# Dashlight.net
KiCad netlist of a schematic drawn in EasyEDA
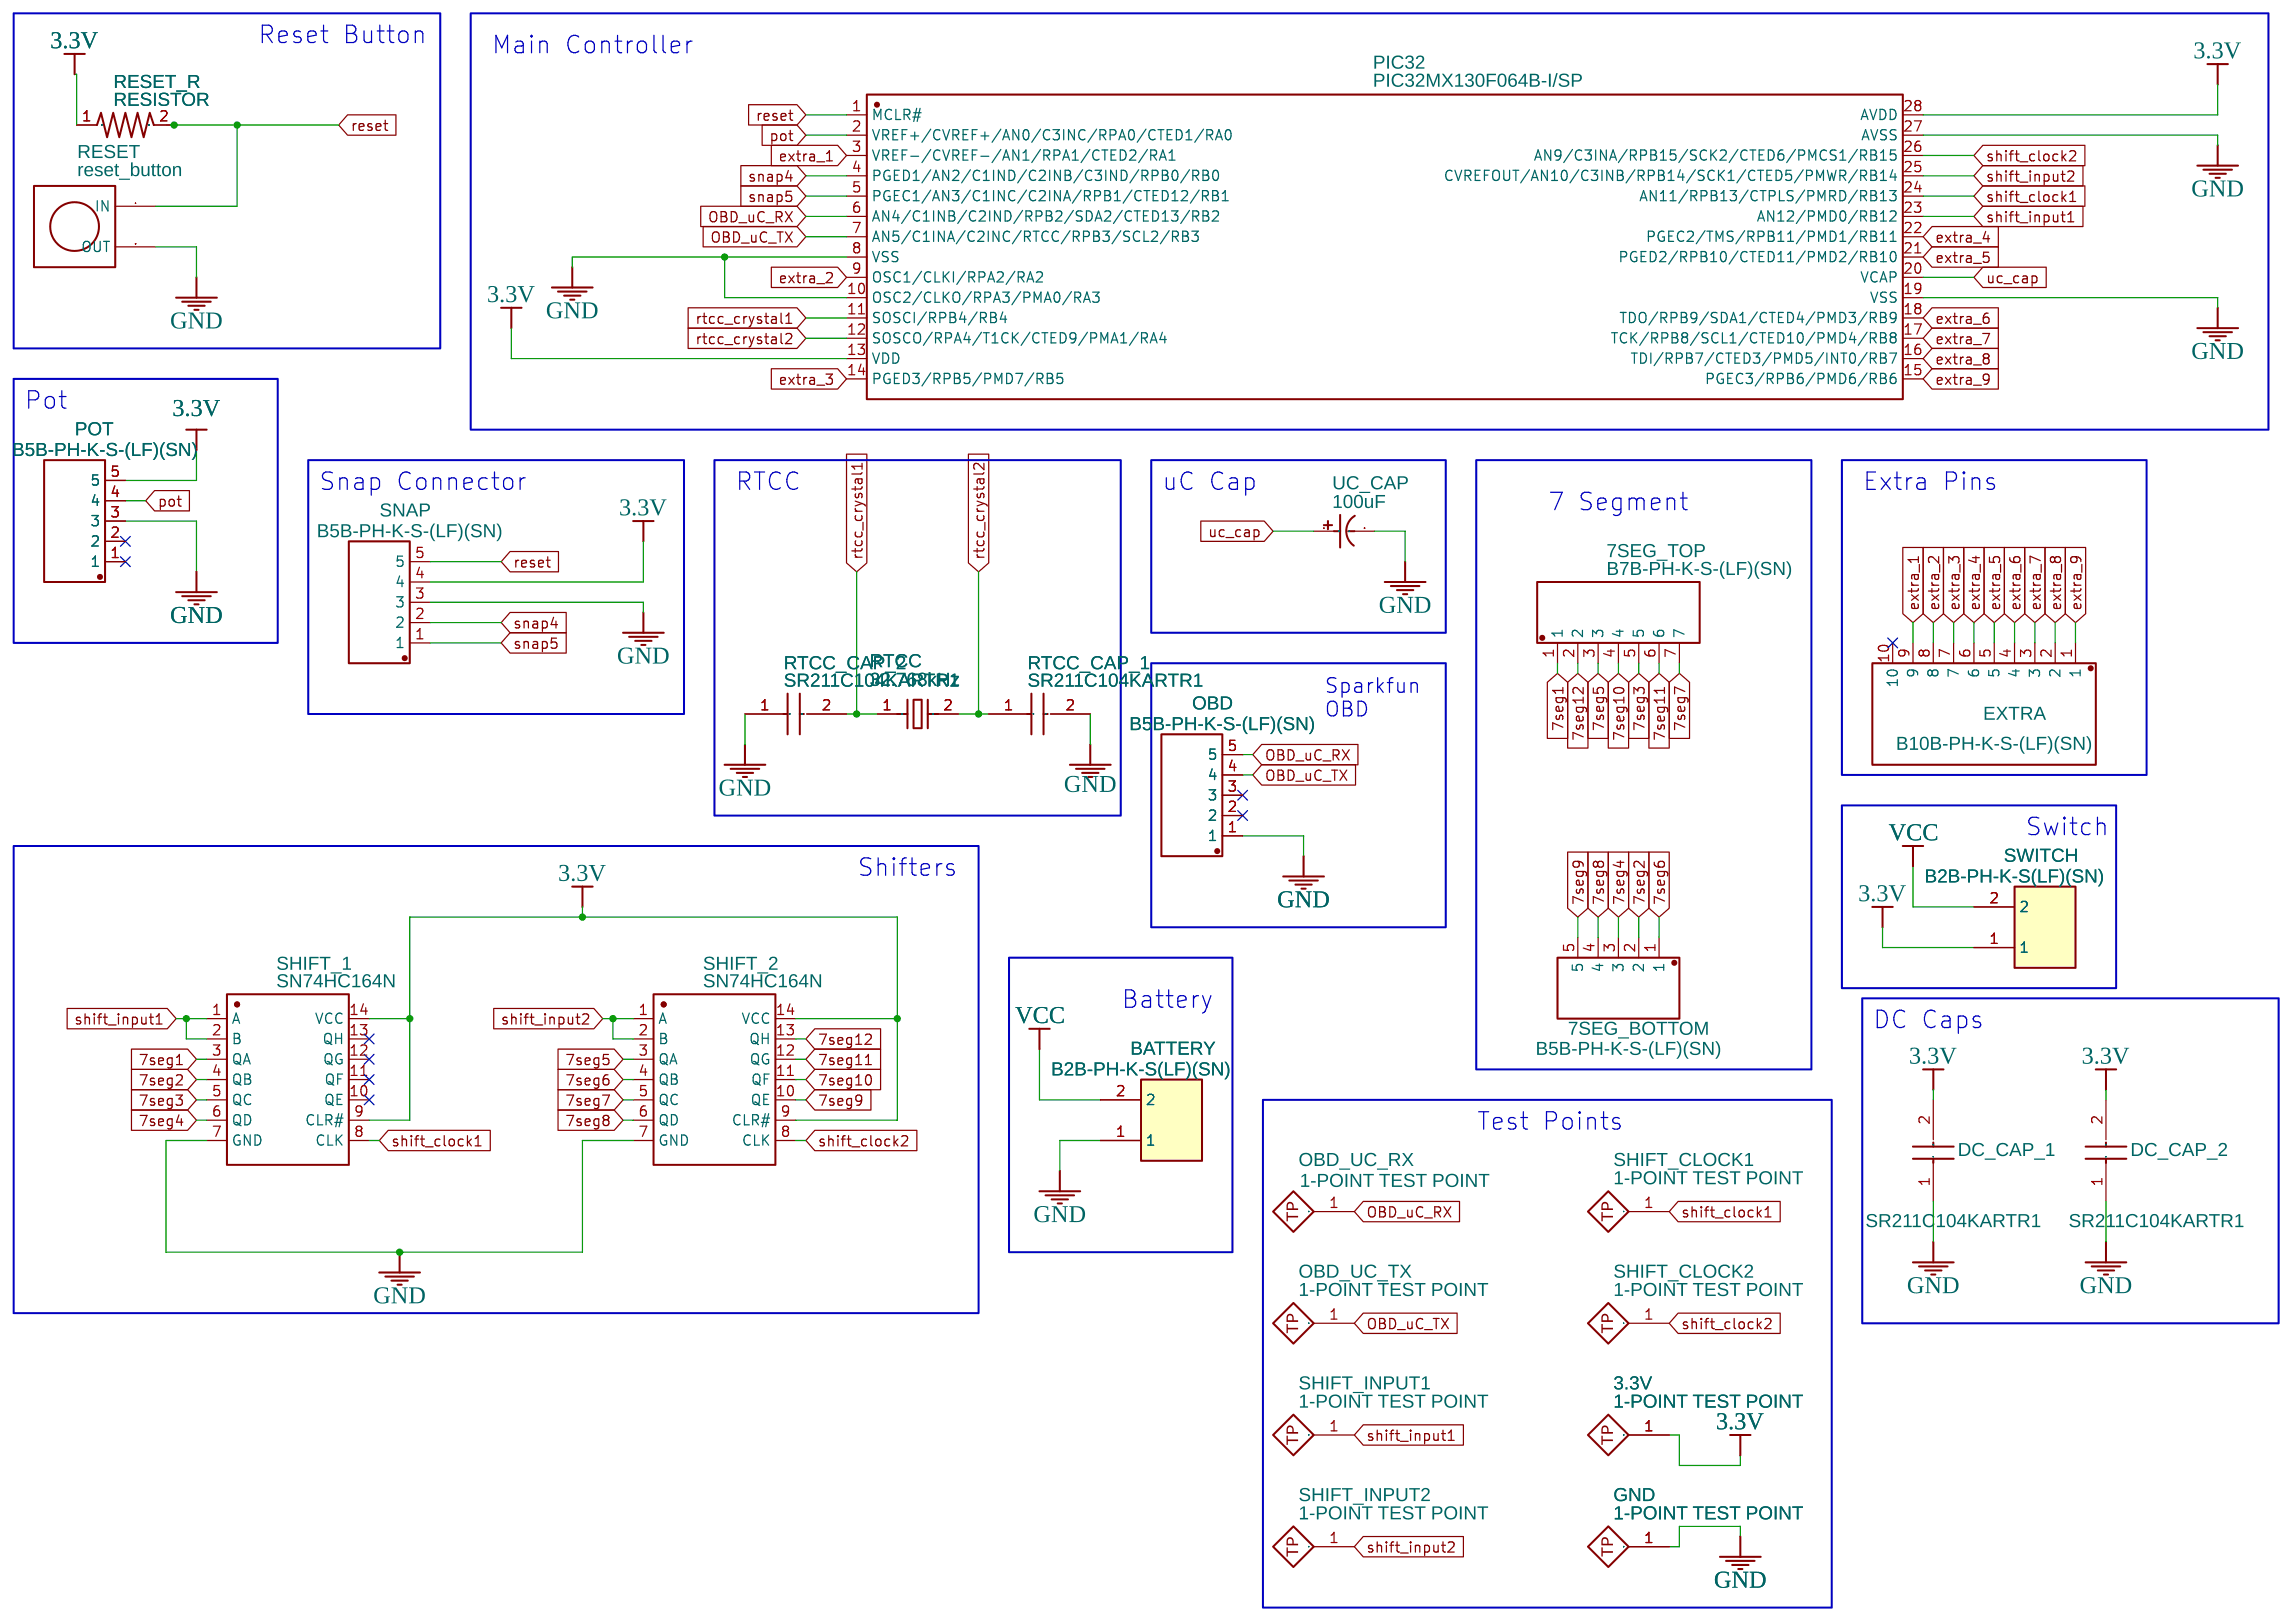
[diagram p0: schematic sheet]

(export (version "E")
  (design (tool "Eeschema 10.0.6"))
  (components
    (comp (ref "3.3V") (value "1-POINT TEST POINT") (libsource (lib "") (part "1-POINT TEST POINT_4")))
    (comp (ref "7SEG_BOTTOM")
      (value "B5B-PH-K-S-(LF)(SN)")
      (fields (field (name "Manufacturer Part") "B5B-PH-K-S(LF)(SN)") (field (name "Manufacturer") "JST"))
      (libsource (lib "") (part "B5B-PH-K-S-(LF)(SN)_1"))
    )
    (comp (ref "7SEG_TOP")
      (value "B7B-PH-K-S-(LF)(SN)")
      (fields (field (name "Manufacturer Part") "B7B-PH-K-S(LF)(SN)") (field (name "Manufacturer") "JST"))
      (libsource (lib "") (part "B7B-PH-K-S-(LF)(SN)"))
    )
    (comp (ref "BATTERY")
      (value "B2B-PH-K-S(LF)(SN)")
      (fields (field (name "Manufacturer") "JST"))
      (libsource (lib "") (part "B2B-PH-K-S(LF)(SN)_1"))
    )
    (comp (ref "DC_CAP_1") (value "SR211C104KARTR1") (libsource (lib "") (part "SR211C104KARTR1")))
    (comp (ref "DC_CAP_2") (value "SR211C104KARTR1") (libsource (lib "") (part "SR211C104KARTR1")))
    (comp (ref "EXTRA")
      (value "B10B-PH-K-S-(LF)(SN)")
      (fields (field (name "Manufacturer Part") "B10B-PH-K-S(LF)(SN)") (field (name "Manufacturer") "JST"))
      (libsource (lib "") (part "B10B-PH-K-S-(LF)(SN)"))
    )
    (comp (ref "GND") (value "1-POINT TEST POINT") (libsource (lib "") (part "1-POINT TEST POINT_6")))
    (comp (ref "OBD")
      (value "B5B-PH-K-S-(LF)(SN)")
      (fields (field (name "Manufacturer Part") "B5B-PH-K-S(LF)(SN)") (field (name "Manufacturer") "JST"))
      (libsource (lib "") (part "B5B-PH-K-S-(LF)(SN)"))
    )
    (comp (ref "OBD_UC_RX") (value "1-POINT TEST POINT") (libsource (lib "") (part "1-POINT TEST POINT_5")))
    (comp (ref "OBD_UC_TX") (value "1-POINT TEST POINT") (libsource (lib "") (part "1-POINT TEST POINT_1")))
    (comp (ref "PIC32")
      (value "PIC32MX130F064B-I/SP")
      (fields (field (name "Manufacturer") "Microchip Tech"))
      (libsource (lib "") (part "PIC32MX130F064B-I/SP"))
    )
    (comp (ref "POT")
      (value "B5B-PH-K-S-(LF)(SN)")
      (fields (field (name "Manufacturer Part") "B5B-PH-K-S(LF)(SN)") (field (name "Manufacturer") "JST"))
      (libsource (lib "") (part "B5B-PH-K-S-(LF)(SN)_3"))
    )
    (comp (ref "RESET") (value "reset_button") (libsource (lib "") (part "Through-Hole 6x6mm Push Button")))
    (comp (ref "RESET_R") (value "RESISTOR") (libsource (lib "") (part "res")))
    (comp (ref "RTCC")
      (value "32.768kHz")
      (fields (field (name "Manufacturer Part") "MP2032K76812002") (field (name "Manufacturer") "HUAXIN(华昕)"))
      (libsource (lib "") (part "MP4032K76812002"))
    )
    (comp (ref "RTCC_CAP_1") (value "SR211C104KARTR1") (libsource (lib "") (part "SR211C104KARTR1_1")))
    (comp (ref "RTCC_CAP_2") (value "SR211C104KARTR1") (libsource (lib "") (part "SR211C104KARTR1_1")))
    (comp (ref "SHIFT_1")
      (value "SN74HC164N")
      (fields (field (name "Manufacturer") "TI(德州仪器)"))
      (libsource (lib "") (part "SN74HC164N"))
    )
    (comp (ref "SHIFT_2")
      (value "SN74HC164N")
      (fields (field (name "Manufacturer") "TI(德州仪器)"))
      (libsource (lib "") (part "SN74HC164N"))
    )
    (comp (ref "SHIFT_CLOCK1")
      (value "1-POINT TEST POINT")
      (libsource (lib "") (part "1-POINT TEST POINT_3"))
    )
    (comp (ref "SHIFT_CLOCK2")
      (value "1-POINT TEST POINT")
      (libsource (lib "") (part "1-POINT TEST POINT_2"))
    )
    (comp (ref "SHIFT_INPUT1") (value "1-POINT TEST POINT") (libsource (lib "") (part "1-POINT TEST POINT")))
    (comp (ref "SHIFT_INPUT2") (value "1-POINT TEST POINT") (libsource (lib "") (part "1-POINT TEST POINT")))
    (comp (ref "SNAP")
      (value "B5B-PH-K-S-(LF)(SN)")
      (fields (field (name "Manufacturer Part") "B5B-PH-K-S(LF)(SN)") (field (name "Manufacturer") "JST"))
      (libsource (lib "") (part "B5B-PH-K-S-(LF)(SN)_2"))
    )
    (comp (ref "SWITCH")
      (value "B2B-PH-K-S(LF)(SN)")
      (fields (field (name "Manufacturer") "JST"))
      (libsource (lib "") (part "B2B-PH-K-S(LF)(SN)"))
    )
    (comp (ref "UC_CAP")
      (value "100uF")
      (fields (field (name "Manufacturer Part") "100uF 10V 4*7") (field (name "Manufacturer") "LCSC"))
      (libsource (lib "") (part "100uF"))
    )
  )
  (nets
    (net (code "1") (name "3.3V") (class "Default")
      (node (ref "3.3V") (pin "1") (pinfunction "1_1") (pintype "unspecified"))
      (node (ref "DC_CAP_1") (pin "2") (pinfunction "2_2") (pintype "bidirectional"))
      (node (ref "DC_CAP_2") (pin "2") (pinfunction "2_2") (pintype "bidirectional"))
      (node (ref "PIC32") (pin "13") (pinfunction "VDD_13") (pintype "unspecified"))
      (node (ref "PIC32") (pin "28") (pinfunction "AVDD_28") (pintype "unspecified"))
      (node (ref "POT") (pin "5") (pinfunction "5_5") (pintype "unspecified"))
      (node (ref "RESET_R") (pin "1") (pinfunction "1_1") (pintype "unspecified"))
      (node (ref "SHIFT_1") (pin "14") (pinfunction "VCC_14") (pintype "unspecified"))
      (node (ref "SHIFT_1") (pin "9") (pinfunction "CLR#_9") (pintype "unspecified"))
      (node (ref "SHIFT_2") (pin "14") (pinfunction "VCC_14") (pintype "unspecified"))
      (node (ref "SHIFT_2") (pin "9") (pinfunction "CLR#_9") (pintype "unspecified"))
      (node (ref "SNAP") (pin "4") (pinfunction "4_4") (pintype "unspecified"))
      (node (ref "SWITCH") (pin "1") (pinfunction "1_1") (pintype "input"))
    )
    (net (code "2") (name "7seg1") (class "Default")
      (node (ref "7SEG_TOP") (pin "1") (pinfunction "1_1") (pintype "unspecified"))
      (node (ref "SHIFT_1") (pin "3") (pinfunction "QA_3") (pintype "unspecified"))
    )
    (net (code "3") (name "7seg2") (class "Default")
      (node (ref "7SEG_BOTTOM") (pin "2") (pinfunction "2_2") (pintype "unspecified"))
      (node (ref "SHIFT_1") (pin "4") (pinfunction "QB_4") (pintype "unspecified"))
    )
    (net (code "4") (name "7seg3") (class "Default")
      (node (ref "7SEG_TOP") (pin "5") (pinfunction "5_5") (pintype "unspecified"))
      (node (ref "SHIFT_1") (pin "5") (pinfunction "QC_5") (pintype "unspecified"))
    )
    (net (code "5") (name "7seg4") (class "Default")
      (node (ref "7SEG_BOTTOM") (pin "3") (pinfunction "3_3") (pintype "unspecified"))
      (node (ref "SHIFT_1") (pin "6") (pinfunction "QD_6") (pintype "unspecified"))
    )
    (net (code "6") (name "7seg5") (class "Default")
      (node (ref "7SEG_TOP") (pin "3") (pinfunction "3_3") (pintype "unspecified"))
      (node (ref "SHIFT_2") (pin "3") (pinfunction "QA_3") (pintype "unspecified"))
    )
    (net (code "7") (name "7seg6") (class "Default")
      (node (ref "7SEG_BOTTOM") (pin "1") (pinfunction "1_1") (pintype "unspecified"))
      (node (ref "SHIFT_2") (pin "4") (pinfunction "QB_4") (pintype "unspecified"))
    )
    (net (code "8") (name "7seg7") (class "Default")
      (node (ref "7SEG_TOP") (pin "7") (pinfunction "7_7") (pintype "unspecified"))
      (node (ref "SHIFT_2") (pin "5") (pinfunction "QC_5") (pintype "unspecified"))
    )
    (net (code "9") (name "7seg8") (class "Default")
      (node (ref "7SEG_BOTTOM") (pin "4") (pinfunction "4_4") (pintype "unspecified"))
      (node (ref "SHIFT_2") (pin "6") (pinfunction "QD_6") (pintype "unspecified"))
    )
    (net (code "10") (name "7seg9") (class "Default")
      (node (ref "7SEG_BOTTOM") (pin "5") (pinfunction "5_5") (pintype "unspecified"))
      (node (ref "SHIFT_2") (pin "10") (pinfunction "QE_10") (pintype "unspecified"))
    )
    (net (code "11") (name "7seg10") (class "Default")
      (node (ref "7SEG_TOP") (pin "4") (pinfunction "4_4") (pintype "unspecified"))
      (node (ref "SHIFT_2") (pin "11") (pinfunction "QF_11") (pintype "unspecified"))
    )
    (net (code "12") (name "7seg11") (class "Default")
      (node (ref "7SEG_TOP") (pin "6") (pinfunction "6_6") (pintype "unspecified"))
      (node (ref "SHIFT_2") (pin "12") (pinfunction "QG_12") (pintype "unspecified"))
    )
    (net (code "13") (name "7seg12") (class "Default")
      (node (ref "7SEG_TOP") (pin "2") (pinfunction "2_2") (pintype "unspecified"))
      (node (ref "SHIFT_2") (pin "13") (pinfunction "QH_13") (pintype "unspecified"))
    )
    (net (code "14") (name "GND") (class "Default")
      (node (ref "BATTERY") (pin "1") (pinfunction "1_1") (pintype "input"))
      (node (ref "DC_CAP_1") (pin "1") (pinfunction "1_1") (pintype "bidirectional"))
      (node (ref "DC_CAP_2") (pin "1") (pinfunction "1_1") (pintype "bidirectional"))
      (node (ref "GND") (pin "1") (pinfunction "1_1") (pintype "unspecified"))
      (node (ref "OBD") (pin "1") (pinfunction "1_1") (pintype "unspecified"))
      (node (ref "PIC32") (pin "10") (pinfunction "OSC2/CLKO/RPA3/PMA0/RA3_10") (pintype "unspecified"))
      (node (ref "PIC32") (pin "19") (pinfunction "VSS_19") (pintype "unspecified"))
      (node (ref "PIC32") (pin "27") (pinfunction "AVSS_27") (pintype "unspecified"))
      (node (ref "PIC32") (pin "8") (pinfunction "VSS_8") (pintype "unspecified"))
      (node (ref "POT") (pin "3") (pinfunction "3_3") (pintype "unspecified"))
      (node (ref "RESET") (pin "2") (pinfunction "OUT_2") (pintype "unspecified"))
      (node (ref "RTCC_CAP_1") (pin "2") (pinfunction "2_2") (pintype "bidirectional"))
      (node (ref "RTCC_CAP_2") (pin "1") (pinfunction "1_1") (pintype "bidirectional"))
      (node (ref "SHIFT_1") (pin "7") (pinfunction "GND_7") (pintype "unspecified"))
      (node (ref "SHIFT_2") (pin "7") (pinfunction "GND_7") (pintype "unspecified"))
      (node (ref "SNAP") (pin "3") (pinfunction "3_3") (pintype "unspecified"))
      (node (ref "UC_CAP") (pin "2") (pinfunction "2_2") (pintype "input"))
    )
    (net (code "15") (name "OBD_uC_RX") (class "Default")
      (node (ref "OBD") (pin "5") (pinfunction "5_5") (pintype "unspecified"))
      (node (ref "OBD_UC_RX") (pin "1") (pinfunction "1_1") (pintype "unspecified"))
      (node (ref "PIC32") (pin "6") (pinfunction "AN4/C1INB/C2IND/RPB2/SDA2/CTED13/RB2_6") (pintype "unspecified"))
    )
    (net (code "16") (name "OBD_uC_TX") (class "Default")
      (node (ref "OBD") (pin "4") (pinfunction "4_4") (pintype "unspecified"))
      (node (ref "OBD_UC_TX") (pin "1") (pinfunction "1_1") (pintype "unspecified"))
      (node (ref "PIC32") (pin "7") (pinfunction "AN5/C1INA/C2INC/RTCC/RPB3/SCL2/RB3_7") (pintype "unspecified"))
    )
    (net (code "17") (name "VCC") (class "Default")
      (node (ref "BATTERY") (pin "2") (pinfunction "2_2") (pintype "input"))
      (node (ref "SWITCH") (pin "2") (pinfunction "2_2") (pintype "input"))
    )
    (net (code "18") (name "extra_1") (class "Default")
      (node (ref "EXTRA") (pin "9") (pinfunction "9_9") (pintype "unspecified"))
      (node (ref "PIC32") (pin "3") (pinfunction "VREF-/CVREF-/AN1/RPA1/CTED2/RA1_3") (pintype "unspecified"))
    )
    (net (code "19") (name "extra_2") (class "Default")
      (node (ref "EXTRA") (pin "8") (pinfunction "8_8") (pintype "unspecified"))
      (node (ref "PIC32") (pin "9") (pinfunction "OSC1/CLKI/RPA2/RA2_9") (pintype "unspecified"))
    )
    (net (code "20") (name "extra_3") (class "Default")
      (node (ref "EXTRA") (pin "7") (pinfunction "7_7") (pintype "unspecified"))
      (node (ref "PIC32") (pin "14") (pinfunction "PGED3/RPB5/PMD7/RB5_14") (pintype "unspecified"))
    )
    (net (code "21") (name "extra_4") (class "Default")
      (node (ref "EXTRA") (pin "6") (pinfunction "6_6") (pintype "unspecified"))
      (node (ref "PIC32") (pin "22") (pinfunction "PGEC2/TMS/RPB11/PMD1/RB11_22") (pintype "unspecified"))
    )
    (net (code "22") (name "extra_5") (class "Default")
      (node (ref "EXTRA") (pin "5") (pinfunction "5_5") (pintype "unspecified"))
      (node (ref "PIC32") (pin "21") (pinfunction "PGED2/RPB10/CTED11/PMD2/RB10_21") (pintype "unspecified"))
    )
    (net (code "23") (name "extra_6") (class "Default")
      (node (ref "EXTRA") (pin "4") (pinfunction "4_4") (pintype "unspecified"))
      (node (ref "PIC32") (pin "18") (pinfunction "TDO/RPB9/SDA1/CTED4/PMD3/RB9_18") (pintype "unspecified"))
    )
    (net (code "24") (name "extra_7") (class "Default")
      (node (ref "EXTRA") (pin "3") (pinfunction "3_3") (pintype "unspecified"))
      (node (ref "PIC32") (pin "17") (pinfunction "TCK/RPB8/SCL1/CTED10/PMD4/RB8_17") (pintype "unspecified"))
    )
    (net (code "25") (name "extra_8") (class "Default")
      (node (ref "EXTRA") (pin "2") (pinfunction "2_2") (pintype "unspecified"))
      (node (ref "PIC32") (pin "16") (pinfunction "TDI/RPB7/CTED3/PMD5/INT0/RB7_16") (pintype "unspecified"))
    )
    (net (code "26") (name "extra_9") (class "Default")
      (node (ref "EXTRA") (pin "1") (pinfunction "1_1") (pintype "unspecified"))
      (node (ref "PIC32") (pin "15") (pinfunction "PGEC3/RPB6/PMD6/RB6_15") (pintype "unspecified"))
    )
    (net (code "27") (name "pot") (class "Default")
      (node (ref "PIC32") (pin "2") (pinfunction "VREF+/CVREF+/AN0/C3INC/RPA0/CTED1/RA0_2") (pintype "unspecified"))
      (node (ref "POT") (pin "4") (pinfunction "4_4") (pintype "unspecified"))
    )
    (net (code "28") (name "reset") (class "Default")
      (node (ref "PIC32") (pin "1") (pinfunction "MCLR#_1") (pintype "unspecified"))
      (node (ref "RESET") (pin "1") (pinfunction "IN_1") (pintype "unspecified"))
      (node (ref "RESET_R") (pin "2") (pinfunction "2_2") (pintype "unspecified"))
      (node (ref "SNAP") (pin "5") (pinfunction "5_5") (pintype "unspecified"))
    )
    (net (code "29") (name "rtcc_crystal1") (class "Default")
      (node (ref "PIC32") (pin "11") (pinfunction "SOSCI/RPB4/RB4_11") (pintype "unspecified"))
      (node (ref "RTCC") (pin "1") (pinfunction "1_1") (pintype "unspecified"))
      (node (ref "RTCC_CAP_2") (pin "2") (pinfunction "2_2") (pintype "bidirectional"))
    )
    (net (code "30") (name "rtcc_crystal2") (class "Default")
      (node (ref "PIC32") (pin "12") (pinfunction "SOSCO/RPA4/T1CK/CTED9/PMA1/RA4_12") (pintype "unspecified"))
      (node (ref "RTCC") (pin "2") (pinfunction "2_2") (pintype "unspecified"))
      (node (ref "RTCC_CAP_1") (pin "1") (pinfunction "1_1") (pintype "bidirectional"))
    )
    (net (code "31") (name "shift_clock1") (class "Default")
      (node (ref "PIC32") (pin "24") (pinfunction "AN11/RPB13/CTPLS/PMRD/RB13_24") (pintype "unspecified"))
      (node (ref "SHIFT_1") (pin "8") (pinfunction "CLK_8") (pintype "unspecified"))
      (node (ref "SHIFT_CLOCK1") (pin "1") (pinfunction "1_1") (pintype "unspecified"))
    )
    (net (code "32") (name "shift_clock2") (class "Default")
      (node (ref "PIC32") (pin "26") (pinfunction "AN9/C3INA/RPB15/SCK2/CTED6/PMCS1/RB15_26") (pintype "unspecified"))
      (node (ref "SHIFT_2") (pin "8") (pinfunction "CLK_8") (pintype "unspecified"))
      (node (ref "SHIFT_CLOCK2") (pin "1") (pinfunction "1_1") (pintype "unspecified"))
    )
    (net (code "33") (name "shift_input1") (class "Default")
      (node (ref "PIC32") (pin "23") (pinfunction "AN12/PMD0/RB12_23") (pintype "unspecified"))
      (node (ref "SHIFT_1") (pin "1") (pinfunction "A_1") (pintype "unspecified"))
      (node (ref "SHIFT_1") (pin "2") (pinfunction "B_2") (pintype "unspecified"))
      (node (ref "SHIFT_INPUT1") (pin "1") (pinfunction "1_1") (pintype "unspecified"))
    )
    (net (code "34") (name "shift_input2") (class "Default")
      (node (ref "PIC32") (pin "25") (pinfunction "CVREFOUT/AN10/C3INB/RPB14/SCK1/CTED5/PMWR/RB14_25") (pintype "unspecified"))
      (node (ref "SHIFT_2") (pin "1") (pinfunction "A_1") (pintype "unspecified"))
      (node (ref "SHIFT_2") (pin "2") (pinfunction "B_2") (pintype "unspecified"))
      (node (ref "SHIFT_INPUT2") (pin "1") (pinfunction "1_1") (pintype "unspecified"))
    )
    (net (code "35") (name "snap4") (class "Default")
      (node (ref "PIC32") (pin "4") (pinfunction "PGED1/AN2/C1IND/C2INB/C3IND/RPB0/RB0_4") (pintype "unspecified"))
      (node (ref "SNAP") (pin "2") (pinfunction "2_2") (pintype "unspecified"))
    )
    (net (code "36") (name "snap5") (class "Default")
      (node (ref "PIC32") (pin "5") (pinfunction "PGEC1/AN3/C1INC/C2INA/RPB1/CTED12/RB1_5") (pintype "unspecified"))
      (node (ref "SNAP") (pin "1") (pinfunction "1_1") (pintype "unspecified"))
    )
    (net (code "37") (name "uc_cap") (class "Default")
      (node (ref "PIC32") (pin "20") (pinfunction "VCAP_20") (pintype "unspecified"))
      (node (ref "UC_CAP") (pin "1") (pinfunction "1_1") (pintype "input"))
    )
    (net (code "38") (name "unconnected-(EXTRA-Pad10)") (class "Default")
      (node (ref "EXTRA") (pin "10") (pinfunction "10_10") (pintype "unspecified+no_connect"))
    )
    (net (code "39") (name "unconnected-(OBD-Pad2)") (class "Default")
      (node (ref "OBD") (pin "2") (pinfunction "2_2") (pintype "unspecified+no_connect"))
    )
    (net (code "40") (name "unconnected-(OBD-Pad3)") (class "Default")
      (node (ref "OBD") (pin "3") (pinfunction "3_3") (pintype "unspecified+no_connect"))
    )
    (net (code "41") (name "unconnected-(POT-Pad1)") (class "Default")
      (node (ref "POT") (pin "1") (pinfunction "1_1") (pintype "unspecified+no_connect"))
    )
    (net (code "42") (name "unconnected-(POT-Pad2)") (class "Default")
      (node (ref "POT") (pin "2") (pinfunction "2_2") (pintype "unspecified+no_connect"))
    )
    (net (code "43") (name "unconnected-(SHIFT_1-QE-Pad10)") (class "Default")
      (node (ref "SHIFT_1") (pin "10") (pinfunction "QE_10") (pintype "unspecified+no_connect"))
    )
    (net (code "44") (name "unconnected-(SHIFT_1-QF-Pad11)") (class "Default")
      (node (ref "SHIFT_1") (pin "11") (pinfunction "QF_11") (pintype "unspecified+no_connect"))
    )
    (net (code "45") (name "unconnected-(SHIFT_1-QG-Pad12)") (class "Default")
      (node (ref "SHIFT_1") (pin "12") (pinfunction "QG_12") (pintype "unspecified+no_connect"))
    )
    (net (code "46") (name "unconnected-(SHIFT_1-QH-Pad13)") (class "Default")
      (node (ref "SHIFT_1") (pin "13") (pinfunction "QH_13") (pintype "unspecified+no_connect"))
    )
  )
)
